# megaUSB_spider.net
KiCad netlist of a schematic drawn in EAGLE
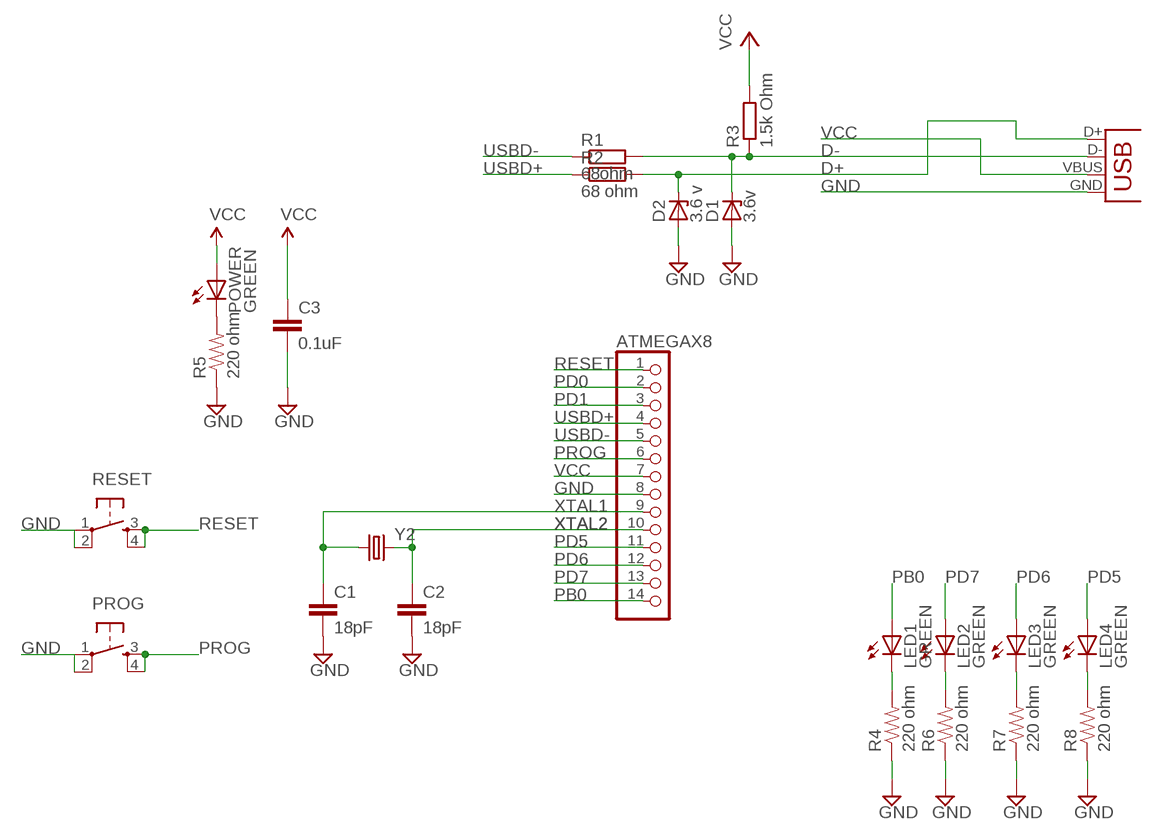
[diagram p0: schematic, sheet 1]

(export (version "E")
  (design (tool "Eeschema 10.0.6"))
  (components
    (comp (ref "ATMEGAX8")
      (value "PINHD-1X14")
      (footprint "eagle-import:1X14")
      (libsource (lib "eagle-import") (part "PINHD-1X14"))
    )
    (comp (ref "C1")
      (value "18pF")
      (footprint "eagle-import:1206")
      (libsource (lib "eagle-import") (part "CAP1206"))
    )
    (comp (ref "C2")
      (value "18pF")
      (footprint "eagle-import:1206")
      (libsource (lib "eagle-import") (part "CAP1206"))
    )
    (comp (ref "C3")
      (value "0.1uF")
      (footprint "eagle-import:1206")
      (libsource (lib "eagle-import") (part "CAP1206"))
    )
    (comp (ref "D1")
      (value "3.6v")
      (footprint "eagle-import:SOT23")
      (libsource (lib "eagle-import") (part "ZENER-DIODESOT23"))
    )
    (comp (ref "D2")
      (value "3.6 v")
      (footprint "eagle-import:SOT23")
      (libsource (lib "eagle-import") (part "ZENER-DIODESOT23"))
    )
    (comp (ref "JP1")
      (value "USBSMD")
      (footprint "eagle-import:USB-MINIB")
      (libsource (lib "eagle-import") (part "USBSMD"))
    )
    (comp (ref "LED1")
      (value "GREEN")
      (footprint "eagle-import:LED-1206")
      (libsource (lib "eagle-import") (part "LED-GREENLARGE"))
    )
    (comp (ref "LED2")
      (value "GREEN")
      (footprint "eagle-import:LED-1206")
      (libsource (lib "eagle-import") (part "LED-GREENLARGE"))
    )
    (comp (ref "LED3")
      (value "GREEN")
      (footprint "eagle-import:LED-1206")
      (libsource (lib "eagle-import") (part "LED-GREENLARGE"))
    )
    (comp (ref "LED4")
      (value "GREEN")
      (footprint "eagle-import:LED-1206")
      (libsource (lib "eagle-import") (part "LED-GREENLARGE"))
    )
    (comp (ref "POWER")
      (value "GREEN")
      (footprint "eagle-import:LED-1206")
      (libsource (lib "eagle-import") (part "LED-GREENLARGE"))
    )
    (comp (ref "PROG")
      (value "TAC_SWITCHPTH")
      (footprint "eagle-import:TACTILE-PTH")
      (libsource (lib "eagle-import") (part "TAC_SWITCHPTH"))
    )
    (comp (ref "R1")
      (value "68ohm")
      (footprint "eagle-import:R0805")
      (libsource (lib "eagle-import") (part "R-EU_R0805"))
    )
    (comp (ref "R2")
      (value "68 ohm")
      (footprint "eagle-import:R0805")
      (libsource (lib "eagle-import") (part "R-EU_R0805"))
    )
    (comp (ref "R3")
      (value "1.5k Ohm")
      (footprint "eagle-import:R1206")
      (libsource (lib "eagle-import") (part "R-EU_R1206"))
    )
    (comp (ref "R4")
      (value "220 ohm")
      (footprint "eagle-import:1206")
      (libsource (lib "eagle-import") (part "RESISTOR1206"))
    )
    (comp (ref "R5")
      (value "220 ohm")
      (footprint "eagle-import:1206")
      (libsource (lib "eagle-import") (part "RESISTOR1206"))
    )
    (comp (ref "R6")
      (value "220 ohm")
      (footprint "eagle-import:1206")
      (libsource (lib "eagle-import") (part "RESISTOR1206"))
    )
    (comp (ref "R7")
      (value "220 ohm")
      (footprint "eagle-import:1206")
      (libsource (lib "eagle-import") (part "RESISTOR1206"))
    )
    (comp (ref "R8")
      (value "220 ohm")
      (footprint "eagle-import:1206")
      (libsource (lib "eagle-import") (part "RESISTOR1206"))
    )
    (comp (ref "RESET")
      (value "TAC_SWITCHPTH")
      (footprint "eagle-import:TACTILE-PTH")
      (libsource (lib "eagle-import") (part "TAC_SWITCHPTH"))
    )
    (comp (ref "Y2")
      (value "CRYSTALHC49US")
      (footprint "eagle-import:HC49US")
      (libsource (lib "eagle-import") (part "CRYSTALHC49US"))
    )
  )
  (nets
    (net (code "1") (name "/D+") (class "Default")
      (node (ref "D2") (pin "3") (pinfunction "C_3") (pintype "passive"))
      (node (ref "JP1") (pin "D+") (pinfunction "D+_D+") (pintype "bidirectional"))
      (node (ref "R2") (pin "2") (pinfunction "2_2") (pintype "passive"))
    )
    (net (code "2") (name "/D-") (class "Default")
      (node (ref "D1") (pin "3") (pinfunction "C_3") (pintype "passive"))
      (node (ref "JP1") (pin "D-") (pinfunction "D-_D-") (pintype "bidirectional"))
      (node (ref "R1") (pin "2") (pinfunction "2_2") (pintype "passive"))
      (node (ref "R3") (pin "1") (pinfunction "1_1") (pintype "passive"))
    )
    (net (code "3") (name "/PB0") (class "Default")
      (node (ref "LED1") (pin "A") (pinfunction "A_A") (pintype "passive"))
    )
    (net (code "4") (name "/PD0") (class "Default")
      (node (ref "ATMEGAX8") (pin "2") (pinfunction "2_2") (pintype "passive"))
    )
    (net (code "5") (name "/PD1") (class "Default")
      (node (ref "ATMEGAX8") (pin "3") (pinfunction "3_3") (pintype "passive"))
    )
    (net (code "6") (name "/PD5") (class "Default")
      (node (ref "ATMEGAX8") (pin "11") (pinfunction "11_11") (pintype "passive"))
      (node (ref "LED4") (pin "A") (pinfunction "A_A") (pintype "passive"))
    )
    (net (code "7") (name "/PD6") (class "Default")
      (node (ref "ATMEGAX8") (pin "12") (pinfunction "12_12") (pintype "passive"))
      (node (ref "LED3") (pin "A") (pinfunction "A_A") (pintype "passive"))
    )
    (net (code "8") (name "/PD7") (class "Default")
      (node (ref "ATMEGAX8") (pin "13") (pinfunction "13_13") (pintype "passive"))
      (node (ref "LED2") (pin "A") (pinfunction "A_A") (pintype "passive"))
    )
    (net (code "9") (name "/PROG") (class "Default")
      (node (ref "ATMEGAX8") (pin "6") (pinfunction "6_6") (pintype "passive"))
      (node (ref "PROG") (pin "3") (pinfunction "3_3") (pintype "passive"))
      (node (ref "PROG") (pin "4") (pinfunction "4_4") (pintype "passive"))
    )
    (net (code "10") (name "/RESET") (class "Default")
      (node (ref "ATMEGAX8") (pin "1") (pinfunction "1_1") (pintype "passive"))
      (node (ref "RESET") (pin "3") (pinfunction "3_3") (pintype "passive"))
      (node (ref "RESET") (pin "4") (pinfunction "4_4") (pintype "passive"))
    )
    (net (code "11") (name "/USBD+") (class "Default")
      (node (ref "ATMEGAX8") (pin "4") (pinfunction "4_4") (pintype "passive"))
      (node (ref "R2") (pin "1") (pinfunction "1_1") (pintype "passive"))
    )
    (net (code "12") (name "/USBD-") (class "Default")
      (node (ref "ATMEGAX8") (pin "5") (pinfunction "5_5") (pintype "passive"))
      (node (ref "R1") (pin "1") (pinfunction "1_1") (pintype "passive"))
    )
    (net (code "13") (name "/XTAL1") (class "Default")
      (node (ref "ATMEGAX8") (pin "9") (pinfunction "9_9") (pintype "passive"))
      (node (ref "C1") (pin "1") (pinfunction "1_1") (pintype "passive"))
      (node (ref "Y2") (pin "1") (pinfunction "1_1") (pintype "passive"))
    )
    (net (code "14") (name "/XTAL2") (class "Default")
      (node (ref "ATMEGAX8") (pin "10") (pinfunction "10_10") (pintype "passive"))
      (node (ref "C2") (pin "1") (pinfunction "1_1") (pintype "passive"))
      (node (ref "Y2") (pin "2") (pinfunction "2_2") (pintype "passive"))
    )
    (net (code "15") (name "GND") (class "Default")
      (node (ref "ATMEGAX8") (pin "8") (pinfunction "8_8") (pintype "passive"))
      (node (ref "C1") (pin "2") (pinfunction "2_2") (pintype "passive"))
      (node (ref "C2") (pin "2") (pinfunction "2_2") (pintype "passive"))
      (node (ref "C3") (pin "2") (pinfunction "2_2") (pintype "passive"))
      (node (ref "D1") (pin "1") (pinfunction "A_1") (pintype "passive"))
      (node (ref "D2") (pin "1") (pinfunction "A_1") (pintype "passive"))
      (node (ref "JP1") (pin "GND") (pinfunction "GND_GND") (pintype "bidirectional"))
      (node (ref "PROG") (pin "1") (pinfunction "1_1") (pintype "passive"))
      (node (ref "PROG") (pin "2") (pinfunction "2_2") (pintype "passive"))
      (node (ref "R4") (pin "1") (pinfunction "1_1") (pintype "passive"))
      (node (ref "R5") (pin "1") (pinfunction "1_1") (pintype "passive"))
      (node (ref "R6") (pin "1") (pinfunction "1_1") (pintype "passive"))
      (node (ref "R7") (pin "1") (pinfunction "1_1") (pintype "passive"))
      (node (ref "R8") (pin "1") (pinfunction "1_1") (pintype "passive"))
      (node (ref "RESET") (pin "1") (pinfunction "1_1") (pintype "passive"))
      (node (ref "RESET") (pin "2") (pinfunction "2_2") (pintype "passive"))
    )
    (net (code "16") (name "Net-(LED1-PadC)") (class "Default")
      (node (ref "LED1") (pin "C") (pinfunction "C_C") (pintype "passive"))
      (node (ref "R4") (pin "2") (pinfunction "2_2") (pintype "passive"))
    )
    (net (code "17") (name "Net-(LED2-PadC)") (class "Default")
      (node (ref "LED2") (pin "C") (pinfunction "C_C") (pintype "passive"))
      (node (ref "R6") (pin "2") (pinfunction "2_2") (pintype "passive"))
    )
    (net (code "18") (name "Net-(LED3-PadC)") (class "Default")
      (node (ref "LED3") (pin "C") (pinfunction "C_C") (pintype "passive"))
      (node (ref "R7") (pin "2") (pinfunction "2_2") (pintype "passive"))
    )
    (net (code "19") (name "Net-(LED4-PadC)") (class "Default")
      (node (ref "LED4") (pin "C") (pinfunction "C_C") (pintype "passive"))
      (node (ref "R8") (pin "2") (pinfunction "2_2") (pintype "passive"))
    )
    (net (code "20") (name "Net-(POWER-PadC)") (class "Default")
      (node (ref "POWER") (pin "C") (pinfunction "C_C") (pintype "passive"))
      (node (ref "R5") (pin "2") (pinfunction "2_2") (pintype "passive"))
    )
    (net (code "21") (name "VCC") (class "Default")
      (node (ref "ATMEGAX8") (pin "7") (pinfunction "7_7") (pintype "passive"))
      (node (ref "C3") (pin "1") (pinfunction "1_1") (pintype "passive"))
      (node (ref "JP1") (pin "VBUS") (pinfunction "VBUS_VBUS") (pintype "bidirectional"))
      (node (ref "POWER") (pin "A") (pinfunction "A_A") (pintype "passive"))
      (node (ref "R3") (pin "2") (pinfunction "2_2") (pintype "passive"))
    )
    (net (code "22") (name "unconnected-(ATMEGAX8-Pad14)") (class "Default")
      (node (ref "ATMEGAX8") (pin "14") (pinfunction "14_14") (pintype "passive"))
    )
  )
)
